# RC__TX.net
KiCad netlist of a schematic drawn in EAGLE
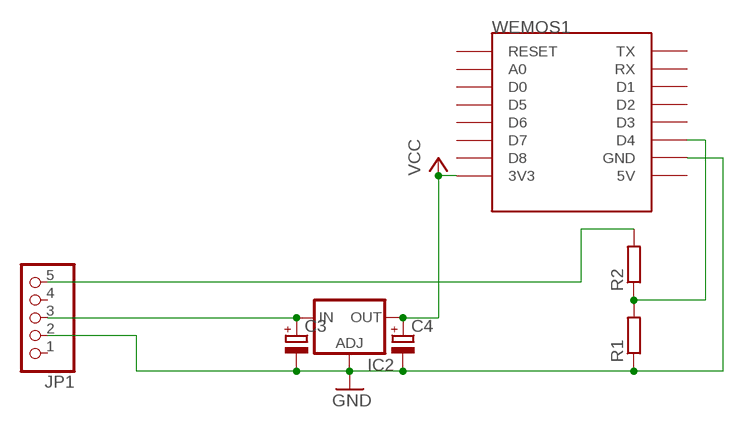
[diagram p0: schematic, sheet 1]

(export (version "E")
  (design (tool "Eeschema 10.0.6"))
  (components
    (comp (ref "C3")
      (value "CPOL-EUE2,5-6E")
      (footprint "eagle-import:E2,5-6E")
      (libsource (lib "eagle-import") (part "CPOL-EUE2,5-6E"))
    )
    (comp (ref "C4")
      (value "CPOL-EUE2,5-6E")
      (footprint "eagle-import:E2,5-6E")
      (libsource (lib "eagle-import") (part "CPOL-EUE2,5-6E"))
    )
    (comp (ref "IC2")
      (value "LM317TS")
      (footprint "eagle-import:317TS")
      (libsource (lib "eagle-import") (part "LM317TS"))
    )
    (comp (ref "JP1")
      (value "PINHD-1X5")
      (footprint "eagle-import:1X05")
      (libsource (lib "eagle-import") (part "PINHD-1X5"))
    )
    (comp (ref "R1")
      (value "R-EU_0207/10")
      (footprint "eagle-import:0207_10")
      (libsource (lib "eagle-import") (part "R-EU_0207/10"))
    )
    (comp (ref "R2")
      (value "R-EU_0207/10")
      (footprint "eagle-import:0207_10")
      (libsource (lib "eagle-import") (part "R-EU_0207/10"))
    )
    (comp (ref "WEMOS1")
      (value "WEMOS-D1-MINI")
      (footprint "eagle-import:WEMOS-D1-MINI")
      (libsource (lib "eagle-import") (part "WEMOS-D1-MINI"))
    )
  )
  (nets
    (net (code "1") (name "GND") (class "Default")
      (node (ref "C3") (pin "-") (pinfunction "-_-") (pintype "passive"))
      (node (ref "C4") (pin "-") (pinfunction "-_-") (pintype "passive"))
      (node (ref "IC2") (pin "1") (pinfunction "ADJ_1") (pintype "input"))
      (node (ref "JP1") (pin "2") (pinfunction "2_2") (pintype "passive"))
      (node (ref "R1") (pin "1") (pinfunction "1_1") (pintype "passive"))
      (node (ref "WEMOS1") (pin "GND") (pinfunction "GND_GND") (pintype "bidirectional"))
    )
    (net (code "2") (name "Net-(IC2-IN)") (class "Default")
      (node (ref "C3") (pin "+") (pinfunction "+_+") (pintype "passive"))
      (node (ref "IC2") (pin "3") (pinfunction "IN_3") (pintype "input"))
      (node (ref "JP1") (pin "3") (pinfunction "3_3") (pintype "passive"))
    )
    (net (code "3") (name "Net-(JP1-Pad5)") (class "Default")
      (node (ref "JP1") (pin "5") (pinfunction "5_5") (pintype "passive"))
      (node (ref "R2") (pin "2") (pinfunction "2_2") (pintype "passive"))
    )
    (net (code "4") (name "Net-(R1-Pad2)") (class "Default")
      (node (ref "R1") (pin "2") (pinfunction "2_2") (pintype "passive"))
      (node (ref "R2") (pin "1") (pinfunction "1_1") (pintype "passive"))
      (node (ref "WEMOS1") (pin "D4") (pinfunction "D4_D4") (pintype "bidirectional"))
    )
    (net (code "5") (name "VCC") (class "Default")
      (node (ref "C4") (pin "+") (pinfunction "+_+") (pintype "passive"))
      (node (ref "IC2") (pin "2") (pinfunction "OUT_2") (pintype "passive"))
      (node (ref "WEMOS1") (pin "3V3") (pinfunction "3V3_3V3") (pintype "bidirectional"))
    )
    (net (code "6") (name "unconnected-(JP1-Pad1)") (class "Default")
      (node (ref "JP1") (pin "1") (pinfunction "1_1") (pintype "passive"))
    )
    (net (code "7") (name "unconnected-(JP1-Pad4)") (class "Default")
      (node (ref "JP1") (pin "4") (pinfunction "4_4") (pintype "passive"))
    )
    (net (code "8") (name "unconnected-(WEMOS1-Pad5V)") (class "Default")
      (node (ref "WEMOS1") (pin "5V") (pinfunction "5V_5V") (pintype "bidirectional"))
    )
    (net (code "9") (name "unconnected-(WEMOS1-PadA0)") (class "Default")
      (node (ref "WEMOS1") (pin "A0") (pinfunction "A0_A0") (pintype "bidirectional"))
    )
    (net (code "10") (name "unconnected-(WEMOS1-PadD0)") (class "Default")
      (node (ref "WEMOS1") (pin "D0") (pinfunction "D0_D0") (pintype "bidirectional"))
    )
    (net (code "11") (name "unconnected-(WEMOS1-PadD1)") (class "Default")
      (node (ref "WEMOS1") (pin "D1") (pinfunction "D1_D1") (pintype "bidirectional"))
    )
    (net (code "12") (name "unconnected-(WEMOS1-PadD2)") (class "Default")
      (node (ref "WEMOS1") (pin "D2") (pinfunction "D2_D2") (pintype "bidirectional"))
    )
    (net (code "13") (name "unconnected-(WEMOS1-PadD3)") (class "Default")
      (node (ref "WEMOS1") (pin "D3") (pinfunction "D3_D3") (pintype "bidirectional"))
    )
    (net (code "14") (name "unconnected-(WEMOS1-PadD5)") (class "Default")
      (node (ref "WEMOS1") (pin "D5") (pinfunction "D5_D5") (pintype "bidirectional"))
    )
    (net (code "15") (name "unconnected-(WEMOS1-PadD6)") (class "Default")
      (node (ref "WEMOS1") (pin "D6") (pinfunction "D6_D6") (pintype "bidirectional"))
    )
    (net (code "16") (name "unconnected-(WEMOS1-PadD7)") (class "Default")
      (node (ref "WEMOS1") (pin "D7") (pinfunction "D7_D7") (pintype "bidirectional"))
    )
    (net (code "17") (name "unconnected-(WEMOS1-PadD8)") (class "Default")
      (node (ref "WEMOS1") (pin "D8") (pinfunction "D8_D8") (pintype "bidirectional"))
    )
    (net (code "18") (name "unconnected-(WEMOS1-PadRESET)") (class "Default")
      (node (ref "WEMOS1") (pin "RESET") (pinfunction "RESET_RESET") (pintype "bidirectional"))
    )
    (net (code "19") (name "unconnected-(WEMOS1-PadRX)") (class "Default")
      (node (ref "WEMOS1") (pin "RX") (pinfunction "RX_RX") (pintype "bidirectional"))
    )
    (net (code "20") (name "unconnected-(WEMOS1-PadTX)") (class "Default")
      (node (ref "WEMOS1") (pin "TX") (pinfunction "TX_TX") (pintype "bidirectional"))
    )
  )
)
